# PCE_-_TG16.net
KiCad netlist of a schematic drawn in EAGLE
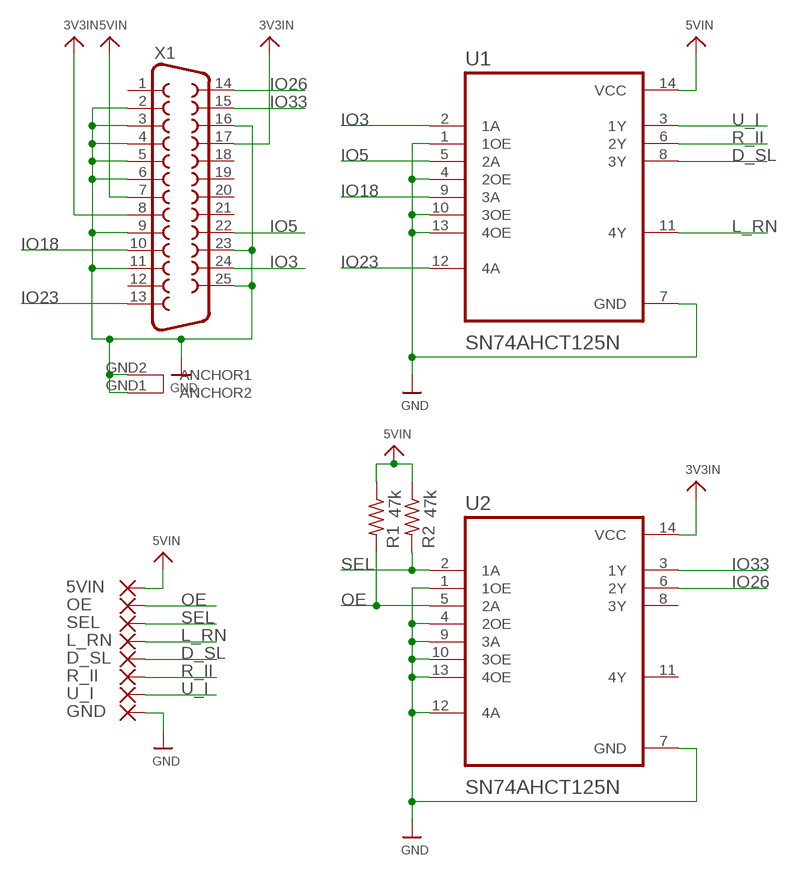
[diagram p0: schematic, sheet 1]

(export (version "E")
  (design (tool "Eeschema 10.0.6"))
  (components
    (comp (ref "5VIN")
      (value "SMD5")
      (footprint "eagle-import:SMD2,54-5,08")
      (libsource (lib "eagle-import") (part "SMD5"))
    )
    (comp (ref "D_SL")
      (value "SMD5")
      (footprint "eagle-import:SMD2,54-5,08")
      (libsource (lib "eagle-import") (part "SMD5"))
    )
    (comp (ref "GND")
      (value "SMD5")
      (footprint "eagle-import:SMD2,54-5,08")
      (libsource (lib "eagle-import") (part "SMD5"))
    )
    (comp (ref "L_RN")
      (value "SMD5")
      (footprint "eagle-import:SMD2,54-5,08")
      (libsource (lib "eagle-import") (part "SMD5"))
    )
    (comp (ref "OE")
      (value "SMD5")
      (footprint "eagle-import:SMD2,54-5,08")
      (libsource (lib "eagle-import") (part "SMD5"))
    )
    (comp (ref "R1")
      (value "47k")
      (footprint "eagle-import:R1206")
      (libsource (lib "eagle-import") (part "R-US_R1206"))
    )
    (comp (ref "R2")
      (value "47k")
      (footprint "eagle-import:R1206")
      (libsource (lib "eagle-import") (part "R-US_R1206"))
    )
    (comp (ref "R_II")
      (value "SMD5")
      (footprint "eagle-import:SMD2,54-5,08")
      (libsource (lib "eagle-import") (part "SMD5"))
    )
    (comp (ref "SEL")
      (value "SMD5")
      (footprint "eagle-import:SMD2,54-5,08")
      (libsource (lib "eagle-import") (part "SMD5"))
    )
    (comp (ref "U1")
      (value "SN74AHCT125N")
      (footprint "eagle-import:DIP794W45P254L1969H508Q14")
      (fields (field (name "MF") "Texas Instruments"))
      (libsource (lib "eagle-import") (part "SN74AHCT125N"))
    )
    (comp (ref "U2")
      (value "SN74AHCT125N")
      (footprint "eagle-import:DIP794W45P254L1969H508Q14")
      (fields (field (name "MF") "Texas Instruments"))
      (libsource (lib "eagle-import") (part "SN74AHCT125N"))
    )
    (comp (ref "U_I")
      (value "SMD5")
      (footprint "eagle-import:SMD2,54-5,08")
      (libsource (lib "eagle-import") (part "SMD5"))
    )
    (comp (ref "X1")
      (value "DB25_FEMALEHP")
      (footprint "eagle-import:F25HP")
      (libsource (lib "eagle-import") (part "DB25_FEMALEHP"))
    )
  )
  (nets
    (net (code "1") (name "/D_SL") (class "Default")
      (node (ref "D_SL") (pin "1") (pinfunction "P_1") (pintype "passive"))
      (node (ref "U1") (pin "8") (pinfunction "3Y_8") (pintype "output"))
    )
    (net (code "2") (name "/IO3") (class "Default")
      (node (ref "U1") (pin "2") (pinfunction "1A_2") (pintype "input"))
      (node (ref "X1") (pin "24") (pinfunction "24_24") (pintype "passive"))
    )
    (net (code "3") (name "/IO5") (class "Default")
      (node (ref "U1") (pin "5") (pinfunction "2A_5") (pintype "input"))
      (node (ref "X1") (pin "22") (pinfunction "22_22") (pintype "passive"))
    )
    (net (code "4") (name "/IO18") (class "Default")
      (node (ref "U1") (pin "9") (pinfunction "3A_9") (pintype "input"))
      (node (ref "X1") (pin "10") (pinfunction "10_10") (pintype "passive"))
    )
    (net (code "5") (name "/IO23") (class "Default")
      (node (ref "U1") (pin "12") (pinfunction "4A_12") (pintype "bidirectional"))
      (node (ref "X1") (pin "13") (pinfunction "13_13") (pintype "passive"))
    )
    (net (code "6") (name "/IO26") (class "Default")
      (node (ref "U2") (pin "6") (pinfunction "2Y_6") (pintype "output"))
      (node (ref "X1") (pin "14") (pinfunction "14_14") (pintype "passive"))
    )
    (net (code "7") (name "/IO33") (class "Default")
      (node (ref "U2") (pin "3") (pinfunction "1Y_3") (pintype "output"))
      (node (ref "X1") (pin "15") (pinfunction "15_15") (pintype "passive"))
    )
    (net (code "8") (name "/L_RN") (class "Default")
      (node (ref "L_RN") (pin "1") (pinfunction "P_1") (pintype "passive"))
      (node (ref "U1") (pin "11") (pinfunction "4Y_11") (pintype "output"))
    )
    (net (code "9") (name "/OE") (class "Default")
      (node (ref "OE") (pin "1") (pinfunction "P_1") (pintype "passive"))
      (node (ref "R1") (pin "2") (pinfunction "2_2") (pintype "passive"))
      (node (ref "U2") (pin "5") (pinfunction "2A_5") (pintype "input"))
    )
    (net (code "10") (name "/R_II") (class "Default")
      (node (ref "R_II") (pin "1") (pinfunction "P_1") (pintype "passive"))
      (node (ref "U1") (pin "6") (pinfunction "2Y_6") (pintype "output"))
    )
    (net (code "11") (name "/SEL") (class "Default")
      (node (ref "R2") (pin "2") (pinfunction "2_2") (pintype "passive"))
      (node (ref "SEL") (pin "1") (pinfunction "P_1") (pintype "passive"))
      (node (ref "U2") (pin "2") (pinfunction "1A_2") (pintype "input"))
    )
    (net (code "12") (name "/U_I") (class "Default")
      (node (ref "U1") (pin "3") (pinfunction "1Y_3") (pintype "output"))
      (node (ref "U_I") (pin "1") (pinfunction "P_1") (pintype "passive"))
    )
    (net (code "13") (name "3V3IN") (class "Default")
      (node (ref "U2") (pin "14") (pinfunction "VCC_14") (pintype "power_in"))
      (node (ref "X1") (pin "17") (pinfunction "17_17") (pintype "passive"))
      (node (ref "X1") (pin "8") (pinfunction "8_8") (pintype "passive"))
    )
    (net (code "14") (name "5VIN") (class "Default")
      (node (ref "5VIN") (pin "1") (pinfunction "P_1") (pintype "passive"))
      (node (ref "R1") (pin "1") (pinfunction "1_1") (pintype "passive"))
      (node (ref "R2") (pin "1") (pinfunction "1_1") (pintype "passive"))
      (node (ref "U1") (pin "14") (pinfunction "VCC_14") (pintype "power_in"))
      (node (ref "X1") (pin "7") (pinfunction "7_7") (pintype "passive"))
    )
    (net (code "15") (name "GND") (class "Default")
      (node (ref "GND") (pin "1") (pinfunction "P_1") (pintype "passive"))
      (node (ref "U1") (pin "1") (pinfunction "1OE_1") (pintype "input"))
      (node (ref "U1") (pin "10") (pinfunction "3OE_10") (pintype "input"))
      (node (ref "U1") (pin "13") (pinfunction "4OE_13") (pintype "input"))
      (node (ref "U1") (pin "4") (pinfunction "2OE_4") (pintype "input"))
      (node (ref "U1") (pin "7") (pinfunction "GND_7") (pintype "power_in"))
      (node (ref "U2") (pin "1") (pinfunction "1OE_1") (pintype "input"))
      (node (ref "U2") (pin "10") (pinfunction "3OE_10") (pintype "input"))
      (node (ref "U2") (pin "12") (pinfunction "4A_12") (pintype "bidirectional"))
      (node (ref "U2") (pin "13") (pinfunction "4OE_13") (pintype "input"))
      (node (ref "U2") (pin "4") (pinfunction "2OE_4") (pintype "input"))
      (node (ref "U2") (pin "7") (pinfunction "GND_7") (pintype "power_in"))
      (node (ref "U2") (pin "9") (pinfunction "3A_9") (pintype "input"))
      (node (ref "X1") (pin "11") (pinfunction "11_11") (pintype "passive"))
      (node (ref "X1") (pin "16") (pinfunction "16_16") (pintype "passive"))
      (node (ref "X1") (pin "2") (pinfunction "2_2") (pintype "passive"))
      (node (ref "X1") (pin "23") (pinfunction "23_23") (pintype "passive"))
      (node (ref "X1") (pin "25") (pinfunction "25_25") (pintype "passive"))
      (node (ref "X1") (pin "3") (pinfunction "3_3") (pintype "passive"))
      (node (ref "X1") (pin "4") (pinfunction "4_4") (pintype "passive"))
      (node (ref "X1") (pin "5") (pinfunction "5_5") (pintype "passive"))
      (node (ref "X1") (pin "6") (pinfunction "6_6") (pintype "passive"))
      (node (ref "X1") (pin "9") (pinfunction "9_9") (pintype "passive"))
      (node (ref "X1") (pin "GND1") (pinfunction "ANCHOR2_GND1") (pintype "bidirectional"))
      (node (ref "X1") (pin "GND2") (pinfunction "ANCHOR1_GND2") (pintype "bidirectional"))
    )
    (net (code "16") (name "unconnected-(U2-3Y-Pad8)") (class "Default")
      (node (ref "U2") (pin "8") (pinfunction "3Y_8") (pintype "output"))
    )
    (net (code "17") (name "unconnected-(U2-4Y-Pad11)") (class "Default")
      (node (ref "U2") (pin "11") (pinfunction "4Y_11") (pintype "output"))
    )
    (net (code "18") (name "unconnected-(X1-Pad1)") (class "Default")
      (node (ref "X1") (pin "1") (pinfunction "1_1") (pintype "passive"))
    )
    (net (code "19") (name "unconnected-(X1-Pad12)") (class "Default")
      (node (ref "X1") (pin "12") (pinfunction "12_12") (pintype "passive"))
    )
    (net (code "20") (name "unconnected-(X1-Pad18)") (class "Default")
      (node (ref "X1") (pin "18") (pinfunction "18_18") (pintype "passive"))
    )
    (net (code "21") (name "unconnected-(X1-Pad19)") (class "Default")
      (node (ref "X1") (pin "19") (pinfunction "19_19") (pintype "passive"))
    )
    (net (code "22") (name "unconnected-(X1-Pad20)") (class "Default")
      (node (ref "X1") (pin "20") (pinfunction "20_20") (pintype "passive"))
    )
    (net (code "23") (name "unconnected-(X1-Pad21)") (class "Default")
      (node (ref "X1") (pin "21") (pinfunction "21_21") (pintype "passive"))
    )
  )
)
